# ACRoBaT_-_main_board.net
KiCad netlist of a schematic drawn in EAGLE
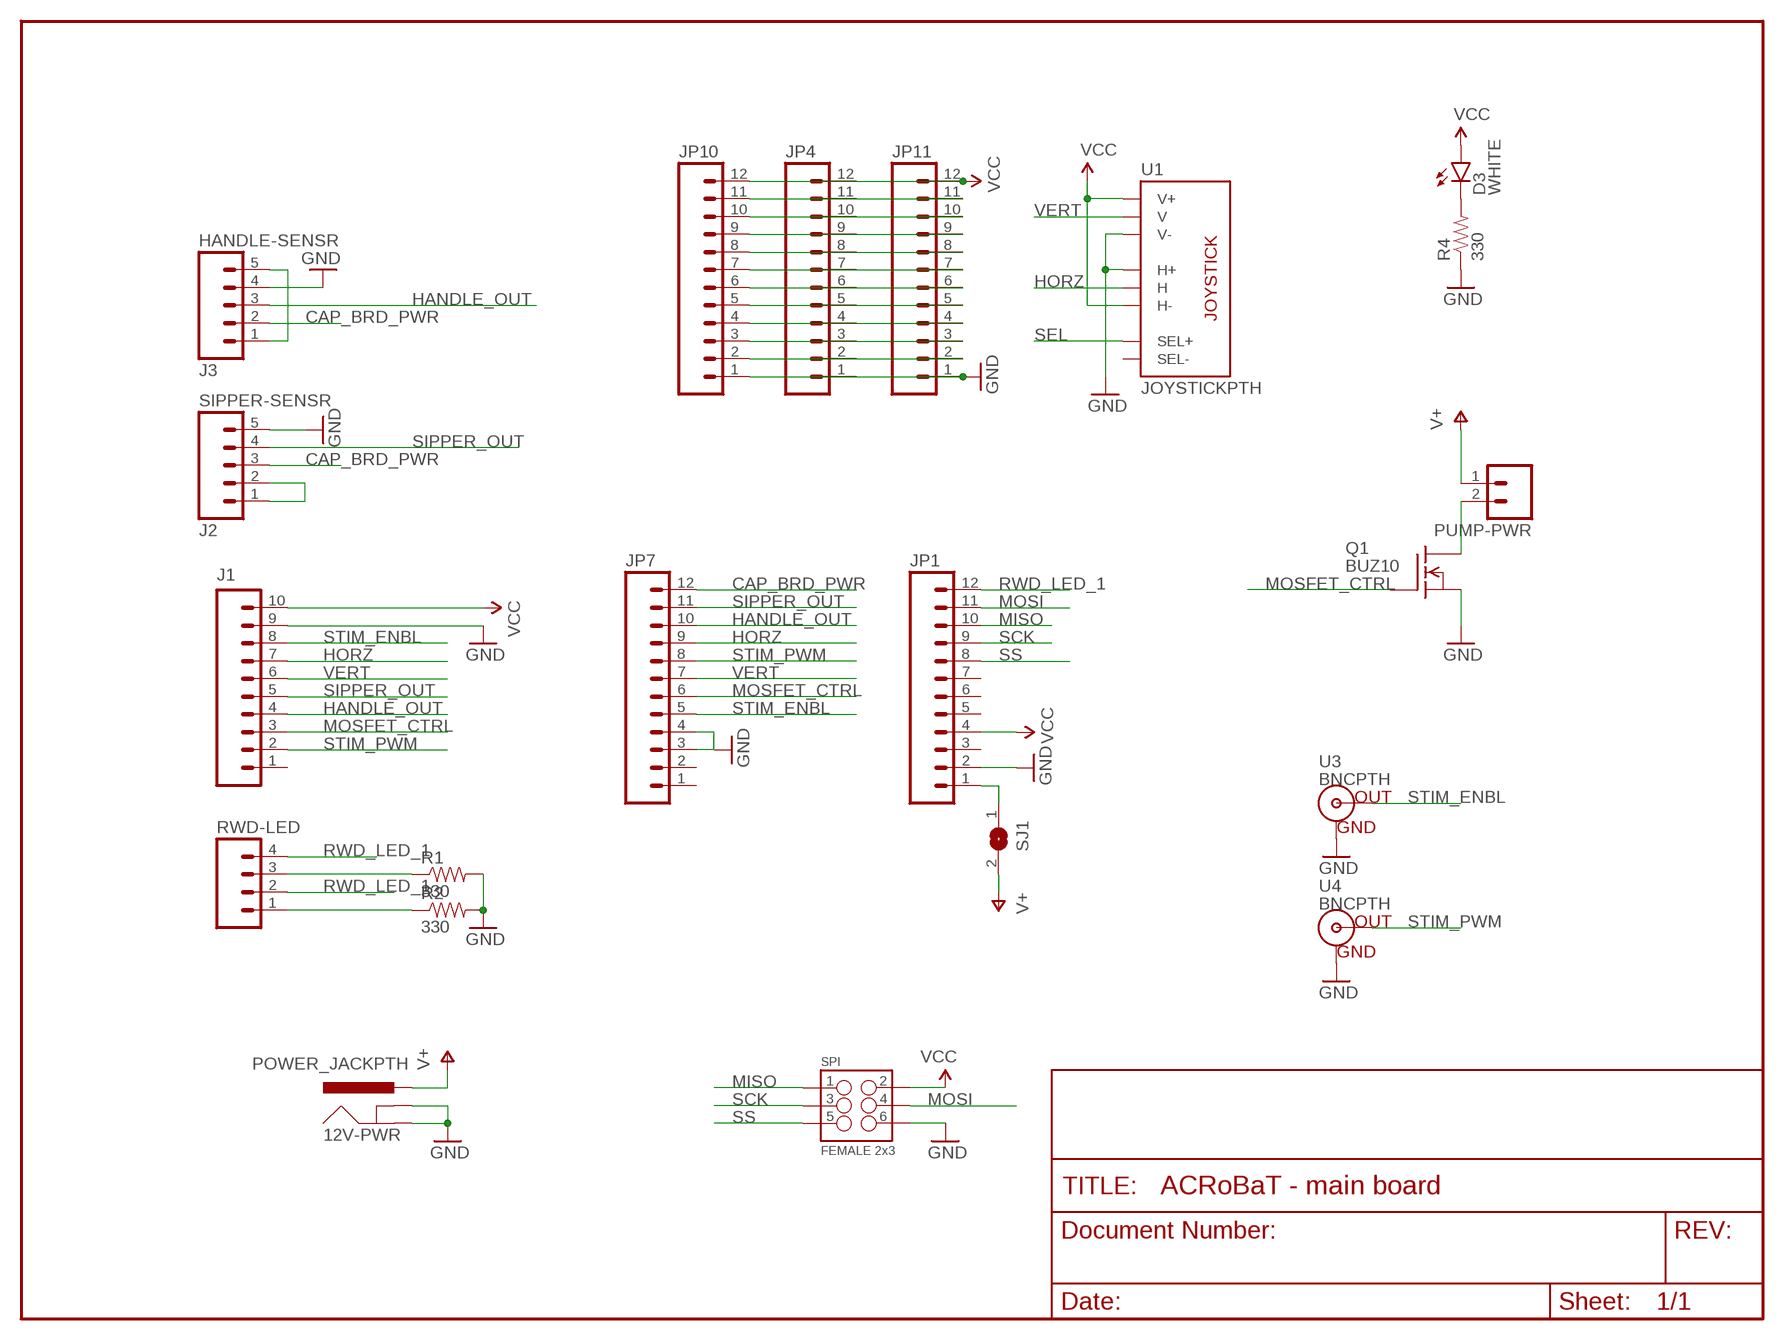
[diagram p0: schematic, sheet 1]

(export (version "E")
  (design (tool "Eeschema 10.0.6"))
  (components
    (comp (ref "12V-PWR")
      (value "POWER_JACKPTH")
      (footprint "eagle-import:POWER_JACK_PTH")
      (libsource (lib "eagle-import") (part "POWER_JACKPTH"))
    )
    (comp (ref "D3")
      (value "WHITE")
      (footprint "eagle-import:LED-1206")
      (libsource (lib "eagle-import") (part "LED-WHITE1206"))
    )
    (comp (ref "HANDLE-SENSR")
      (value "J3")
      (footprint "eagle-import:1X05")
      (libsource (lib "eagle-import") (part "M05PTH"))
    )
    (comp (ref "J1")
      (value "M10SILK_FEMALE_PTH")
      (footprint "eagle-import:1X10")
      (libsource (lib "eagle-import") (part "M10SILK_FEMALE_PTH"))
    )
    (comp (ref "JP1")
      (value "M12PTH")
      (footprint "eagle-import:1X12")
      (libsource (lib "eagle-import") (part "M12PTH"))
    )
    (comp (ref "JP4")
      (value "M12PTH")
      (footprint "eagle-import:1X12")
      (libsource (lib "eagle-import") (part "M12PTH"))
    )
    (comp (ref "JP7")
      (value "M12PTH")
      (footprint "eagle-import:1X12")
      (libsource (lib "eagle-import") (part "M12PTH"))
    )
    (comp (ref "JP10")
      (value "M12PTH")
      (footprint "eagle-import:1X12")
      (libsource (lib "eagle-import") (part "M12PTH"))
    )
    (comp (ref "JP11")
      (value "M12PTH")
      (footprint "eagle-import:1X12")
      (libsource (lib "eagle-import") (part "M12PTH"))
    )
    (comp (ref "PUMP-PWR")
      (value "M02PTH")
      (footprint "eagle-import:1X02")
      (libsource (lib "eagle-import") (part "M02PTH"))
    )
    (comp (ref "Q1")
      (value "BUZ10")
      (footprint "eagle-import:TO220")
      (libsource (lib "eagle-import") (part "BUZ10"))
    )
    (comp (ref "R1")
      (value "330")
      (footprint "eagle-import:AXIAL-0.3")
      (libsource (lib "eagle-import") (part "RESISTORAXIAL-0.3"))
    )
    (comp (ref "R2")
      (value "330")
      (footprint "eagle-import:AXIAL-0.3")
      (libsource (lib "eagle-import") (part "RESISTORAXIAL-0.3"))
    )
    (comp (ref "R4")
      (value "330")
      (footprint "eagle-import:AXIAL-0.3")
      (libsource (lib "eagle-import") (part "RESISTORAXIAL-0.3"))
    )
    (comp (ref "RWD-LED")
      (value "M04PTH")
      (footprint "eagle-import:1X04")
      (libsource (lib "eagle-import") (part "M04PTH"))
    )
    (comp (ref "SIPPER-SENSR")
      (value "J2")
      (footprint "eagle-import:1X05")
      (libsource (lib "eagle-import") (part "M05PTH"))
    )
    (comp (ref "SJ1") (value "SJ") (footprint "eagle-import:SJ") (libsource (lib "eagle-import") (part "SJ")))
    (comp (ref "SPI")
      (value "FEMALE 2x3")
      (footprint "eagle-import:2X3")
      (libsource (lib "eagle-import") (part "M03X2FEMALE"))
    )
    (comp (ref "U1")
      (value "JOYSTICKPTH")
      (footprint "eagle-import:JOYSTICK")
      (libsource (lib "eagle-import") (part "JOYSTICKPTH"))
    )
    (comp (ref "U3")
      (value "BNCPTH")
      (footprint "eagle-import:BNC")
      (libsource (lib "eagle-import") (part "BNCPTH"))
    )
    (comp (ref "U4")
      (value "BNCPTH")
      (footprint "eagle-import:BNC")
      (libsource (lib "eagle-import") (part "BNCPTH"))
    )
  )
  (nets
    (net (code "1") (name "/CAP_BRD_PWR") (class "Default")
      (node (ref "HANDLE-SENSR") (pin "2") (pinfunction "2_2") (pintype "passive"))
      (node (ref "JP7") (pin "12") (pinfunction "12_12") (pintype "passive"))
      (node (ref "SIPPER-SENSR") (pin "3") (pinfunction "3_3") (pintype "passive"))
    )
    (net (code "2") (name "/HANDLE_OUT") (class "Default")
      (node (ref "HANDLE-SENSR") (pin "3") (pinfunction "3_3") (pintype "passive"))
      (node (ref "J1") (pin "4") (pinfunction "4_4") (pintype "passive"))
      (node (ref "JP7") (pin "10") (pinfunction "10_10") (pintype "passive"))
    )
    (net (code "3") (name "/HORZ") (class "Default")
      (node (ref "J1") (pin "7") (pinfunction "7_7") (pintype "passive"))
      (node (ref "JP7") (pin "9") (pinfunction "9_9") (pintype "passive"))
      (node (ref "U1") (pin "H2") (pinfunction "H_H2") (pintype "bidirectional"))
    )
    (net (code "4") (name "/MISO") (class "Default")
      (node (ref "JP1") (pin "10") (pinfunction "10_10") (pintype "passive"))
      (node (ref "SPI") (pin "1") (pinfunction "1_1") (pintype "bidirectional"))
    )
    (net (code "5") (name "/MOSFET_CTRL") (class "Default")
      (node (ref "J1") (pin "3") (pinfunction "3_3") (pintype "passive"))
      (node (ref "JP7") (pin "6") (pinfunction "6_6") (pintype "passive"))
      (node (ref "Q1") (pin "1") (pinfunction "G_1") (pintype "passive"))
    )
    (net (code "6") (name "/MOSI") (class "Default")
      (node (ref "JP1") (pin "11") (pinfunction "11_11") (pintype "passive"))
      (node (ref "SPI") (pin "4") (pinfunction "4_4") (pintype "bidirectional"))
    )
    (net (code "7") (name "/RWD_LED_1") (class "Default")
      (node (ref "JP1") (pin "12") (pinfunction "12_12") (pintype "passive"))
      (node (ref "RWD-LED") (pin "2") (pinfunction "2_2") (pintype "passive"))
      (node (ref "RWD-LED") (pin "4") (pinfunction "4_4") (pintype "passive"))
    )
    (net (code "8") (name "/SCK") (class "Default")
      (node (ref "JP1") (pin "9") (pinfunction "9_9") (pintype "passive"))
      (node (ref "SPI") (pin "3") (pinfunction "3_3") (pintype "bidirectional"))
    )
    (net (code "9") (name "/SEL") (class "Default")
      (node (ref "U1") (pin "B1A") (pinfunction "SEL+_B1A") (pintype "bidirectional"))
    )
    (net (code "10") (name "/SIPPER_OUT") (class "Default")
      (node (ref "J1") (pin "5") (pinfunction "5_5") (pintype "passive"))
      (node (ref "JP7") (pin "11") (pinfunction "11_11") (pintype "passive"))
      (node (ref "SIPPER-SENSR") (pin "4") (pinfunction "4_4") (pintype "passive"))
    )
    (net (code "11") (name "/SS") (class "Default")
      (node (ref "JP1") (pin "8") (pinfunction "8_8") (pintype "passive"))
      (node (ref "SPI") (pin "5") (pinfunction "5_5") (pintype "bidirectional"))
    )
    (net (code "12") (name "/STIM_ENBL") (class "Default")
      (node (ref "J1") (pin "8") (pinfunction "8_8") (pintype "passive"))
      (node (ref "JP7") (pin "5") (pinfunction "5_5") (pintype "passive"))
      (node (ref "U3") (pin "S") (pinfunction "OUT_S") (pintype "bidirectional"))
    )
    (net (code "13") (name "/STIM_PWM") (class "Default")
      (node (ref "J1") (pin "2") (pinfunction "2_2") (pintype "passive"))
      (node (ref "JP7") (pin "8") (pinfunction "8_8") (pintype "passive"))
      (node (ref "U4") (pin "S") (pinfunction "OUT_S") (pintype "bidirectional"))
    )
    (net (code "14") (name "/VERT") (class "Default")
      (node (ref "J1") (pin "6") (pinfunction "6_6") (pintype "passive"))
      (node (ref "JP7") (pin "7") (pinfunction "7_7") (pintype "passive"))
      (node (ref "U1") (pin "V2") (pinfunction "V_V2") (pintype "bidirectional"))
    )
    (net (code "15") (name "GND") (class "Default")
      (node (ref "12V-PWR") (pin "GND") (pinfunction "GND_GND") (pintype "bidirectional"))
      (node (ref "12V-PWR") (pin "GNDBREAK") (pinfunction "GNDBREAK_GNDBREAK") (pintype "bidirectional"))
      (node (ref "HANDLE-SENSR") (pin "4") (pinfunction "4_4") (pintype "passive"))
      (node (ref "J1") (pin "9") (pinfunction "9_9") (pintype "passive"))
      (node (ref "JP1") (pin "2") (pinfunction "2_2") (pintype "passive"))
      (node (ref "JP10") (pin "1") (pinfunction "1_1") (pintype "passive"))
      (node (ref "JP11") (pin "1") (pinfunction "1_1") (pintype "passive"))
      (node (ref "JP4") (pin "1") (pinfunction "1_1") (pintype "passive"))
      (node (ref "JP7") (pin "3") (pinfunction "3_3") (pintype "passive"))
      (node (ref "JP7") (pin "4") (pinfunction "4_4") (pintype "passive"))
      (node (ref "Q1") (pin "3") (pinfunction "S_3") (pintype "passive"))
      (node (ref "R1") (pin "P$2") (pinfunction "2_P$2") (pintype "passive"))
      (node (ref "R2") (pin "P$2") (pinfunction "2_P$2") (pintype "passive"))
      (node (ref "R4") (pin "P$1") (pinfunction "1_P$1") (pintype "passive"))
      (node (ref "SIPPER-SENSR") (pin "5") (pinfunction "5_5") (pintype "passive"))
      (node (ref "SPI") (pin "6") (pinfunction "6_6") (pintype "bidirectional"))
      (node (ref "U1") (pin "H1") (pinfunction "H+_H1") (pintype "bidirectional"))
      (node (ref "U1") (pin "V3") (pinfunction "V-_V3") (pintype "bidirectional"))
      (node (ref "U3") (pin "GND") (pinfunction "GND_GND") (pintype "bidirectional"))
      (node (ref "U4") (pin "GND") (pinfunction "GND_GND") (pintype "bidirectional"))
    )
    (net (code "16") (name "Net-(HANDLE-SENSR-Pad1)") (class "Default")
      (node (ref "HANDLE-SENSR") (pin "1") (pinfunction "1_1") (pintype "passive"))
      (node (ref "HANDLE-SENSR") (pin "5") (pinfunction "5_5") (pintype "passive"))
    )
    (net (code "17") (name "Net-(JP1-Pad1)") (class "Default")
      (node (ref "JP1") (pin "1") (pinfunction "1_1") (pintype "passive"))
      (node (ref "SJ1") (pin "1") (pinfunction "1_1") (pintype "passive"))
    )
    (net (code "18") (name "Net-(JP10-Pad2)") (class "Default")
      (node (ref "JP10") (pin "2") (pinfunction "2_2") (pintype "passive"))
      (node (ref "JP11") (pin "2") (pinfunction "2_2") (pintype "passive"))
      (node (ref "JP4") (pin "2") (pinfunction "2_2") (pintype "passive"))
    )
    (net (code "19") (name "Net-(JP10-Pad3)") (class "Default")
      (node (ref "JP10") (pin "3") (pinfunction "3_3") (pintype "passive"))
      (node (ref "JP11") (pin "3") (pinfunction "3_3") (pintype "passive"))
      (node (ref "JP4") (pin "3") (pinfunction "3_3") (pintype "passive"))
    )
    (net (code "20") (name "Net-(JP10-Pad4)") (class "Default")
      (node (ref "JP10") (pin "4") (pinfunction "4_4") (pintype "passive"))
      (node (ref "JP11") (pin "4") (pinfunction "4_4") (pintype "passive"))
      (node (ref "JP4") (pin "4") (pinfunction "4_4") (pintype "passive"))
    )
    (net (code "21") (name "Net-(JP10-Pad5)") (class "Default")
      (node (ref "JP10") (pin "5") (pinfunction "5_5") (pintype "passive"))
      (node (ref "JP11") (pin "5") (pinfunction "5_5") (pintype "passive"))
      (node (ref "JP4") (pin "5") (pinfunction "5_5") (pintype "passive"))
    )
    (net (code "22") (name "Net-(JP10-Pad6)") (class "Default")
      (node (ref "JP10") (pin "6") (pinfunction "6_6") (pintype "passive"))
      (node (ref "JP11") (pin "6") (pinfunction "6_6") (pintype "passive"))
      (node (ref "JP4") (pin "6") (pinfunction "6_6") (pintype "passive"))
    )
    (net (code "23") (name "Net-(JP10-Pad7)") (class "Default")
      (node (ref "JP10") (pin "7") (pinfunction "7_7") (pintype "passive"))
      (node (ref "JP11") (pin "7") (pinfunction "7_7") (pintype "passive"))
      (node (ref "JP4") (pin "7") (pinfunction "7_7") (pintype "passive"))
    )
    (net (code "24") (name "Net-(JP10-Pad8)") (class "Default")
      (node (ref "JP10") (pin "8") (pinfunction "8_8") (pintype "passive"))
      (node (ref "JP11") (pin "8") (pinfunction "8_8") (pintype "passive"))
      (node (ref "JP4") (pin "8") (pinfunction "8_8") (pintype "passive"))
    )
    (net (code "25") (name "Net-(JP10-Pad9)") (class "Default")
      (node (ref "JP10") (pin "9") (pinfunction "9_9") (pintype "passive"))
      (node (ref "JP11") (pin "9") (pinfunction "9_9") (pintype "passive"))
      (node (ref "JP4") (pin "9") (pinfunction "9_9") (pintype "passive"))
    )
    (net (code "26") (name "Net-(JP10-Pad10)") (class "Default")
      (node (ref "JP10") (pin "10") (pinfunction "10_10") (pintype "passive"))
      (node (ref "JP11") (pin "10") (pinfunction "10_10") (pintype "passive"))
      (node (ref "JP4") (pin "10") (pinfunction "10_10") (pintype "passive"))
    )
    (net (code "27") (name "Net-(JP10-Pad11)") (class "Default")
      (node (ref "JP10") (pin "11") (pinfunction "11_11") (pintype "passive"))
      (node (ref "JP11") (pin "11") (pinfunction "11_11") (pintype "passive"))
      (node (ref "JP4") (pin "11") (pinfunction "11_11") (pintype "passive"))
    )
    (net (code "28") (name "Net-(Q1-D)") (class "Default")
      (node (ref "PUMP-PWR") (pin "2") (pinfunction "2_2") (pintype "passive"))
      (node (ref "Q1") (pin "2") (pinfunction "D_2") (pintype "passive"))
    )
    (net (code "29") (name "Net-(R1-1)") (class "Default")
      (node (ref "R1") (pin "P$1") (pinfunction "1_P$1") (pintype "passive"))
      (node (ref "RWD-LED") (pin "3") (pinfunction "3_3") (pintype "passive"))
    )
    (net (code "30") (name "Net-(R2-1)") (class "Default")
      (node (ref "R2") (pin "P$1") (pinfunction "1_P$1") (pintype "passive"))
      (node (ref "RWD-LED") (pin "1") (pinfunction "1_1") (pintype "passive"))
    )
    (net (code "31") (name "Net-(R4-2)") (class "Default")
      (node (ref "D3") (pin "C") (pinfunction "C_C") (pintype "passive"))
      (node (ref "R4") (pin "P$2") (pinfunction "2_P$2") (pintype "passive"))
    )
    (net (code "32") (name "Net-(SIPPER-SENSR-Pad1)") (class "Default")
      (node (ref "SIPPER-SENSR") (pin "1") (pinfunction "1_1") (pintype "passive"))
      (node (ref "SIPPER-SENSR") (pin "2") (pinfunction "2_2") (pintype "passive"))
    )
    (net (code "33") (name "V+") (class "Default")
      (node (ref "12V-PWR") (pin "PWR") (pinfunction "PWR_PWR") (pintype "bidirectional"))
      (node (ref "PUMP-PWR") (pin "1") (pinfunction "1_1") (pintype "passive"))
      (node (ref "SJ1") (pin "2") (pinfunction "2_2") (pintype "passive"))
    )
    (net (code "34") (name "VCC") (class "Default")
      (node (ref "D3") (pin "A") (pinfunction "A_A") (pintype "passive"))
      (node (ref "J1") (pin "10") (pinfunction "10_10") (pintype "passive"))
      (node (ref "JP1") (pin "4") (pinfunction "4_4") (pintype "passive"))
      (node (ref "JP10") (pin "12") (pinfunction "12_12") (pintype "passive"))
      (node (ref "JP11") (pin "12") (pinfunction "12_12") (pintype "passive"))
      (node (ref "JP4") (pin "12") (pinfunction "12_12") (pintype "passive"))
      (node (ref "SPI") (pin "2") (pinfunction "2_2") (pintype "bidirectional"))
      (node (ref "U1") (pin "H3") (pinfunction "H-_H3") (pintype "bidirectional"))
      (node (ref "U1") (pin "V1") (pinfunction "V+_V1") (pintype "bidirectional"))
    )
    (net (code "35") (name "unconnected-(J1-Pad1)") (class "Default")
      (node (ref "J1") (pin "1") (pinfunction "1_1") (pintype "passive"))
    )
    (net (code "36") (name "unconnected-(JP1-Pad3)") (class "Default")
      (node (ref "JP1") (pin "3") (pinfunction "3_3") (pintype "passive"))
    )
    (net (code "37") (name "unconnected-(JP1-Pad5)") (class "Default")
      (node (ref "JP1") (pin "5") (pinfunction "5_5") (pintype "passive"))
    )
    (net (code "38") (name "unconnected-(JP1-Pad6)") (class "Default")
      (node (ref "JP1") (pin "6") (pinfunction "6_6") (pintype "passive"))
    )
    (net (code "39") (name "unconnected-(JP1-Pad7)") (class "Default")
      (node (ref "JP1") (pin "7") (pinfunction "7_7") (pintype "passive"))
    )
    (net (code "40") (name "unconnected-(JP7-Pad1)") (class "Default")
      (node (ref "JP7") (pin "1") (pinfunction "1_1") (pintype "passive"))
    )
    (net (code "41") (name "unconnected-(JP7-Pad2)") (class "Default")
      (node (ref "JP7") (pin "2") (pinfunction "2_2") (pintype "passive"))
    )
    (net (code "42") (name "unconnected-(U1-SEL--PadB2A)") (class "Default")
      (node (ref "U1") (pin "B2A") (pinfunction "SEL-_B2A") (pintype "bidirectional"))
    )
  )
)
